# Lipo_Rider_Plus.net
KiCad netlist of a schematic drawn in EAGLE
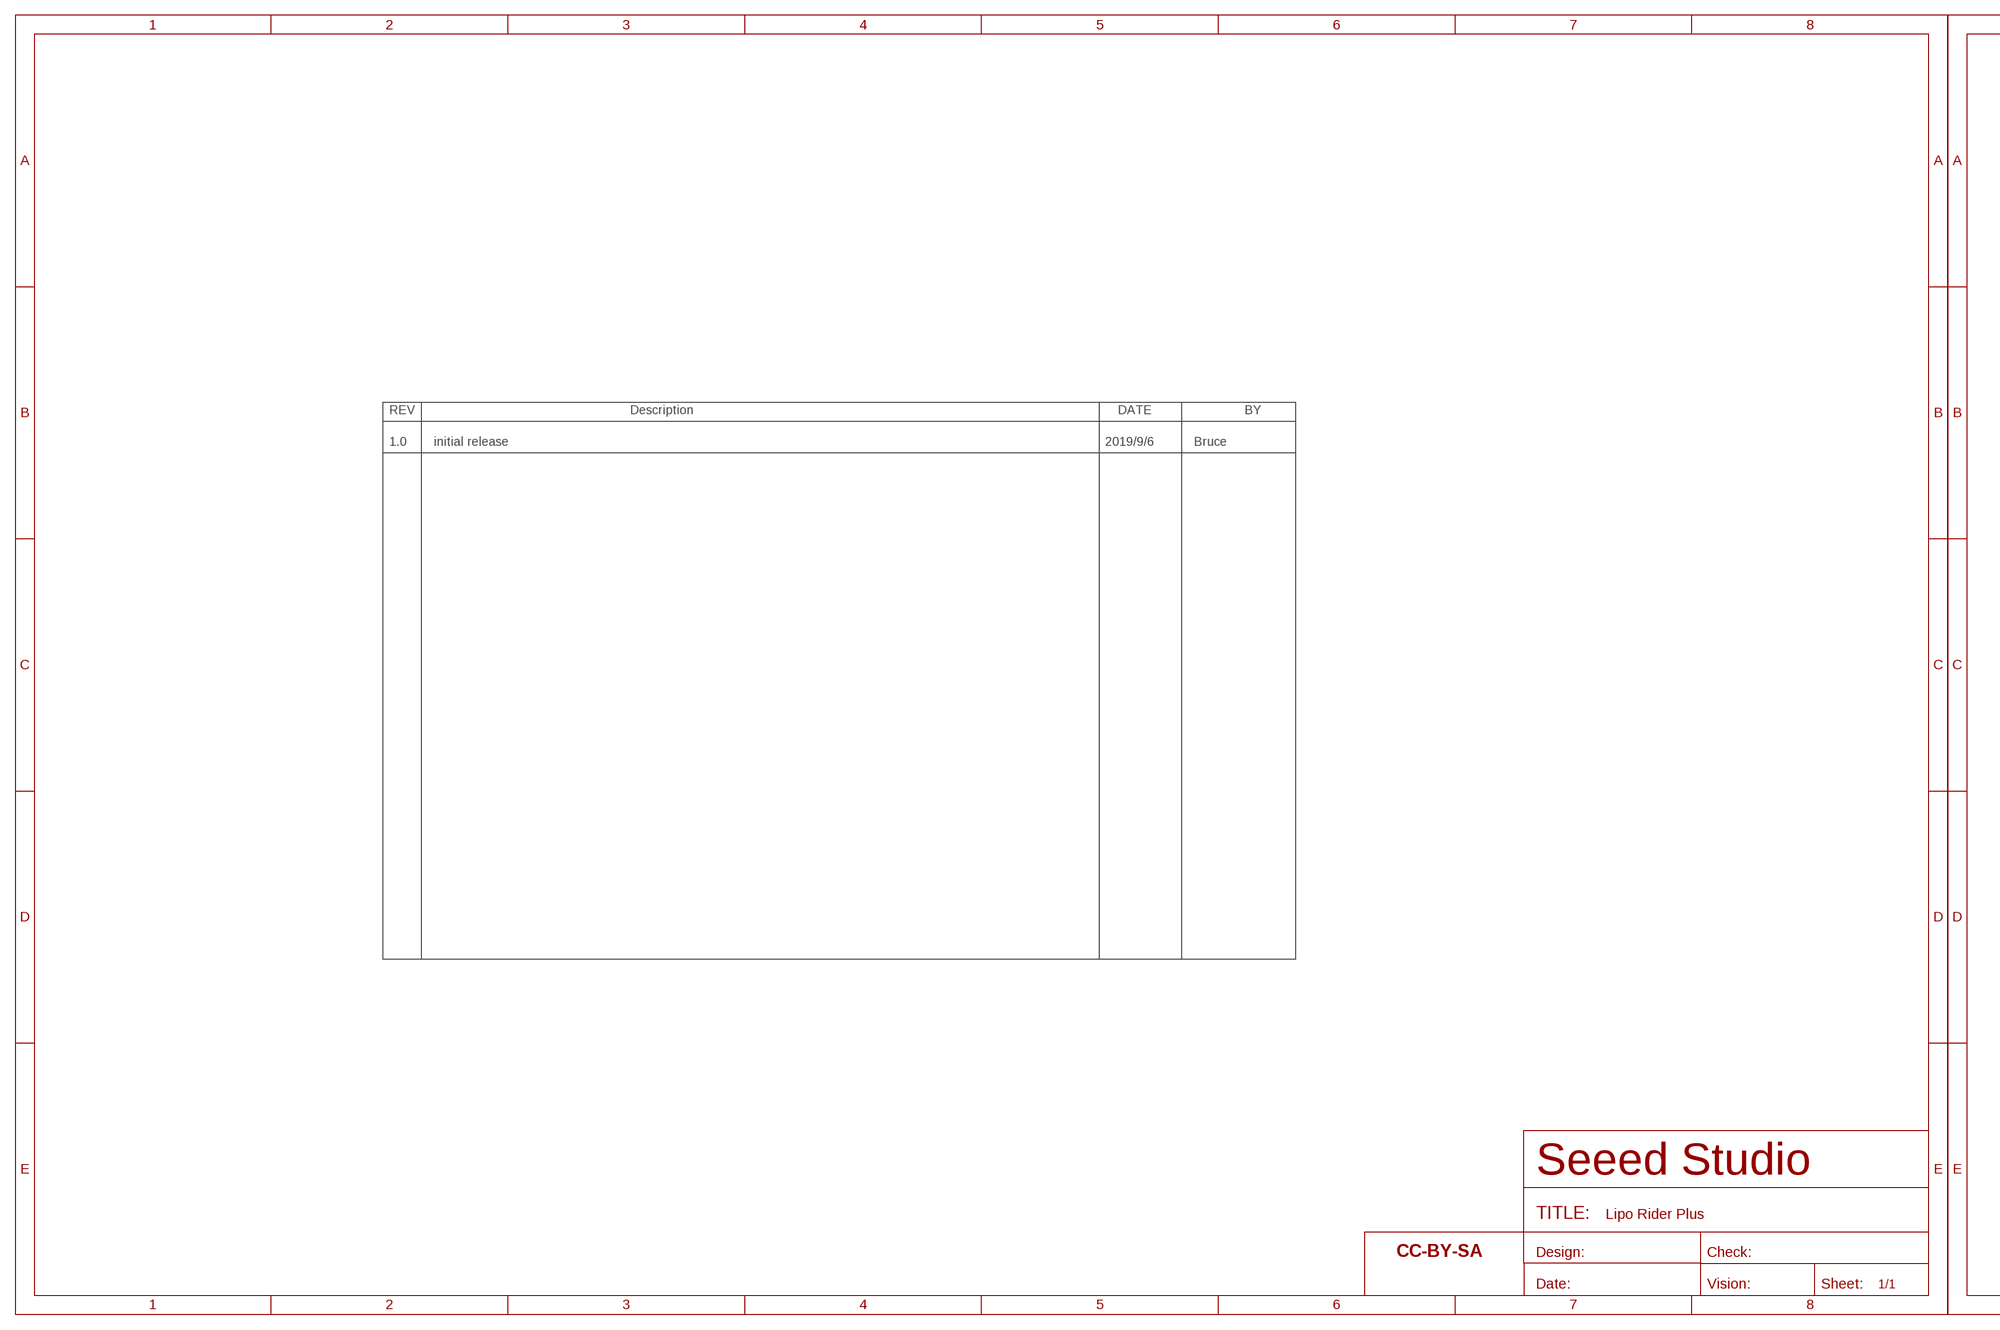
[diagram p0: schematic, sheet 1, part 1 of 2]
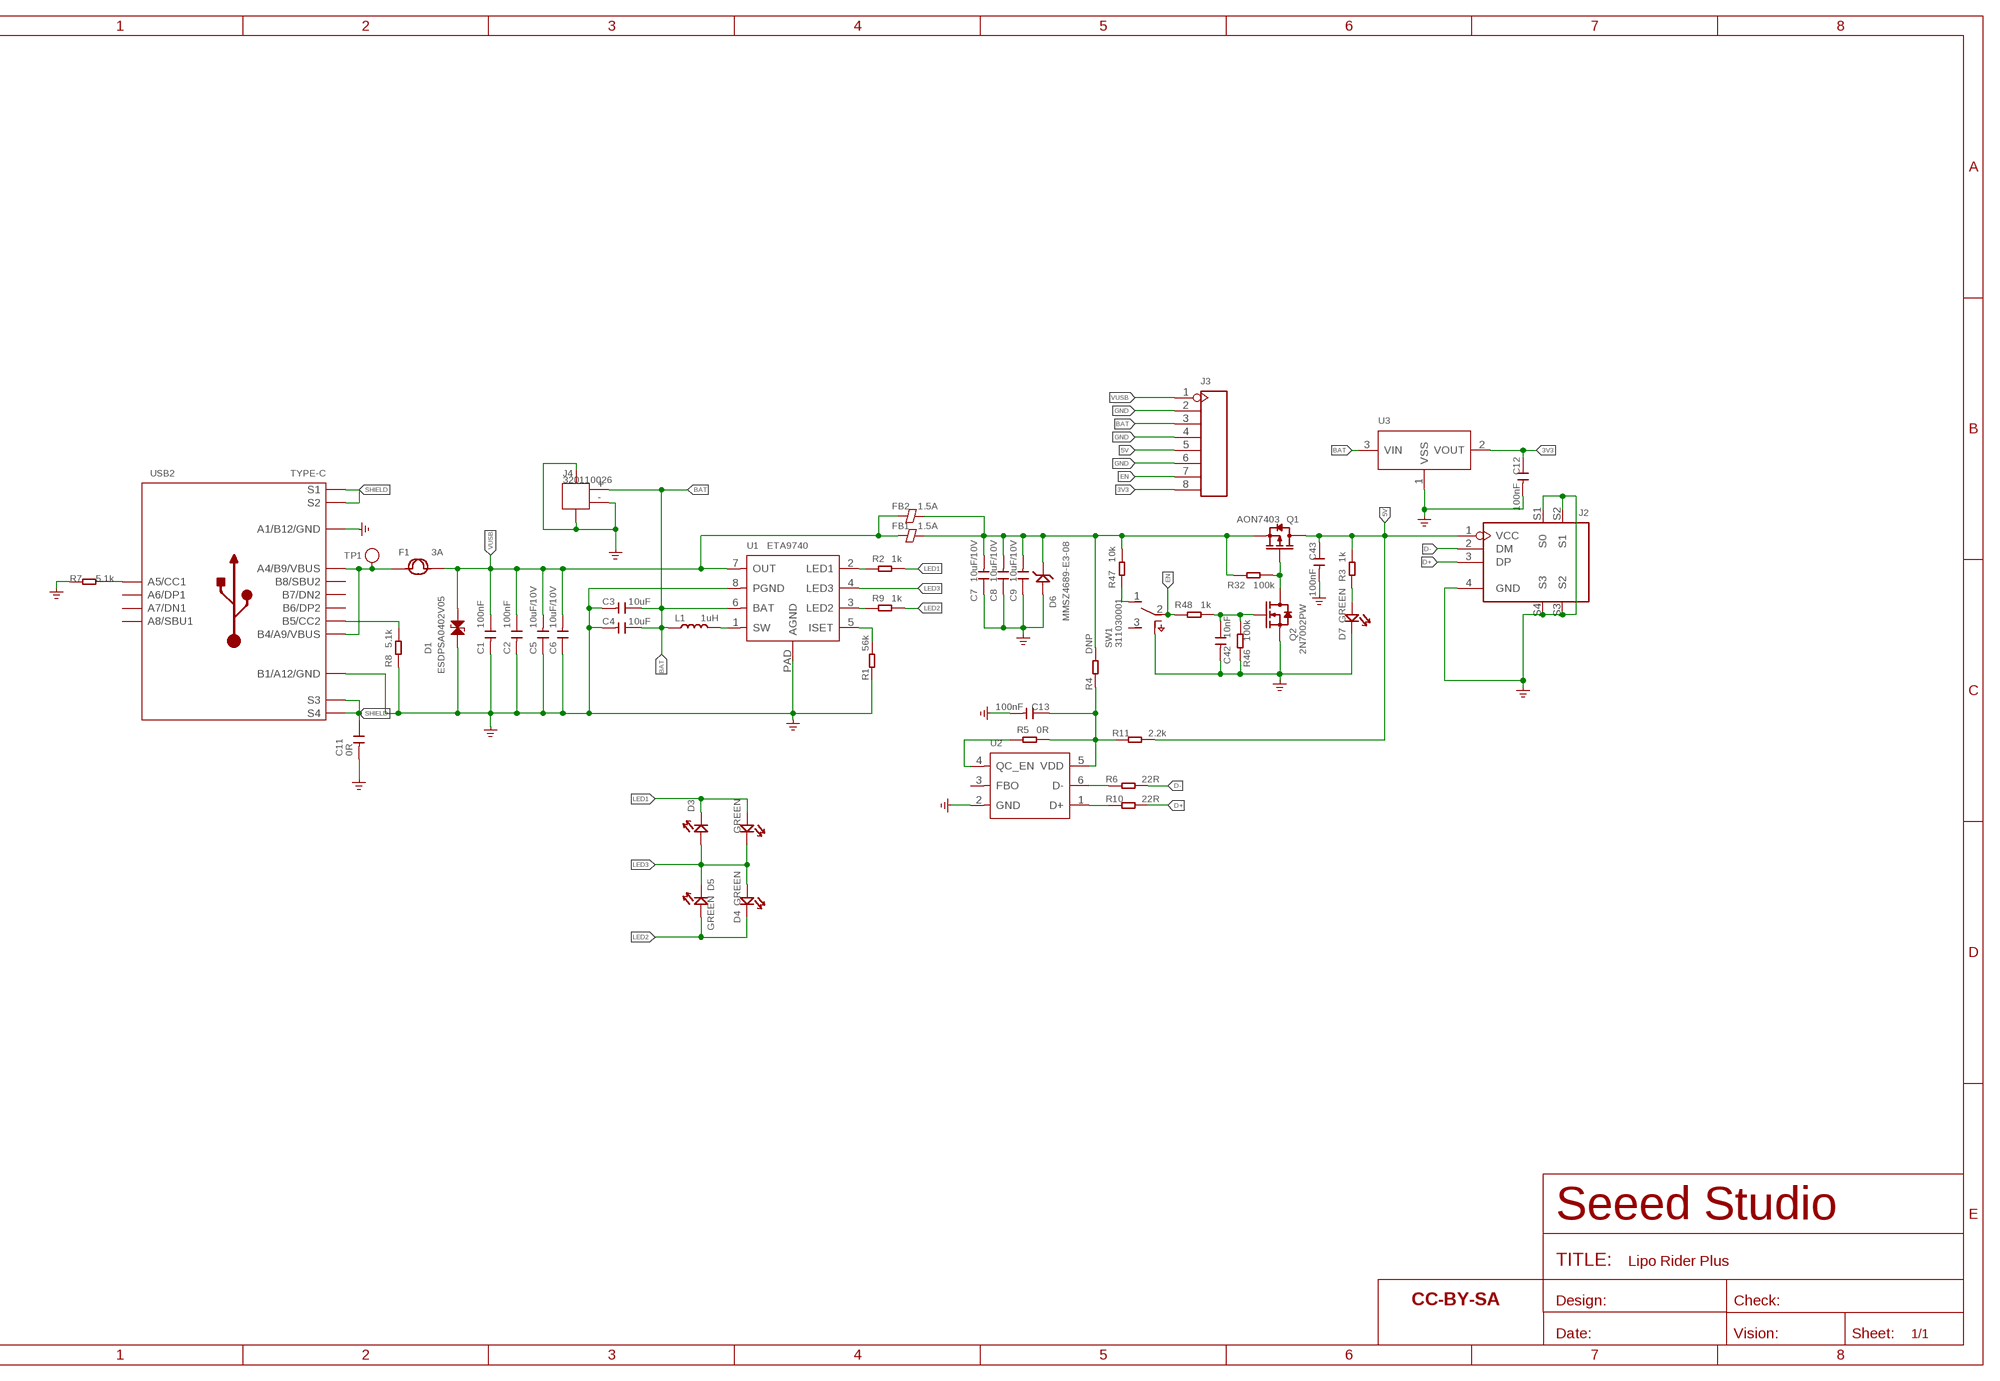
[diagram p1: schematic, sheet 1, part 2 of 2]

(export (version "E")
  (design (tool "Eeschema 10.0.6"))
  (components
    (comp (ref "C1")
      (value "100nF")
      (footprint "eagle-import:C0402")
      (libsource (lib "eagle-import") (part "CAP-0402"))
    )
    (comp (ref "C2")
      (value "100nF")
      (footprint "eagle-import:C0402")
      (libsource (lib "eagle-import") (part "CAP-0402"))
    )
    (comp (ref "C3")
      (value "10uF")
      (footprint "eagle-import:C0603")
      (libsource (lib "eagle-import") (part "CAP-0603"))
    )
    (comp (ref "C4")
      (value "10uF")
      (footprint "eagle-import:C0603")
      (libsource (lib "eagle-import") (part "CAP-0603"))
    )
    (comp (ref "C5")
      (value "10uF/10V")
      (footprint "eagle-import:C0805")
      (libsource (lib "eagle-import") (part "CAP-0805"))
    )
    (comp (ref "C6")
      (value "10uF/10V")
      (footprint "eagle-import:C0805")
      (libsource (lib "eagle-import") (part "CAP-0805"))
    )
    (comp (ref "C7")
      (value "10uF/10V")
      (footprint "eagle-import:C0805")
      (libsource (lib "eagle-import") (part "CAP-0805"))
    )
    (comp (ref "C8")
      (value "10uF/10V")
      (footprint "eagle-import:C0805")
      (libsource (lib "eagle-import") (part "CAP-0805"))
    )
    (comp (ref "C9")
      (value "10uF/10V")
      (footprint "eagle-import:C0805")
      (libsource (lib "eagle-import") (part "CAP-0805"))
    )
    (comp (ref "C11")
      (value "0R")
      (footprint "eagle-import:C0402")
      (libsource (lib "eagle-import") (part "CAP-0402"))
    )
    (comp (ref "C12")
      (value "100nF")
      (footprint "eagle-import:C0402")
      (libsource (lib "eagle-import") (part "CAP-0402"))
    )
    (comp (ref "C13")
      (value "100nF")
      (footprint "eagle-import:C0402")
      (libsource (lib "eagle-import") (part "CAP-0402"))
    )
    (comp (ref "C42")
      (value "10nF")
      (footprint "eagle-import:C0402")
      (libsource (lib "eagle-import") (part "CAP-0402"))
    )
    (comp (ref "C43")
      (value "100nF")
      (footprint "eagle-import:C0402")
      (libsource (lib "eagle-import") (part "CAP-0402"))
    )
    (comp (ref "D1")
      (value "ESDPSA0402V05")
      (footprint "eagle-import:ESD-0402")
      (libsource (lib "eagle-import") (part "D-ESD-2P-DOUBLE-0402"))
    )
    (comp (ref "D2")
      (value "GREEN")
      (footprint "eagle-import:LED-0402")
      (libsource (lib "eagle-import") (part "LED-0402"))
    )
    (comp (ref "D3")
      (value "GREEN")
      (footprint "eagle-import:LED-0402")
      (libsource (lib "eagle-import") (part "LED-0402"))
    )
    (comp (ref "D4")
      (value "GREEN")
      (footprint "eagle-import:LED-0402")
      (libsource (lib "eagle-import") (part "LED-0402"))
    )
    (comp (ref "D5")
      (value "GREEN")
      (footprint "eagle-import:LED-0402")
      (libsource (lib "eagle-import") (part "LED-0402"))
    )
    (comp (ref "D6")
      (value "MMSZ4689-E3-08")
      (footprint "eagle-import:SOD-123")
      (libsource (lib "eagle-import") (part "D-ZENER-2P-304030008"))
    )
    (comp (ref "D7")
      (value "GREEN")
      (footprint "eagle-import:LED-0402")
      (libsource (lib "eagle-import") (part "LED-0402"))
    )
    (comp (ref "F1")
      (value "3A")
      (footprint "eagle-import:F1812")
      (libsource (lib "eagle-import") (part "FUSE'1812'"))
    )
    (comp (ref "FB1")
      (value "1.5A")
      (footprint "eagle-import:F0805")
      (libsource (lib "eagle-import") (part "FERRITE-BEAD-0805"))
    )
    (comp (ref "FB2")
      (value "1.5A")
      (footprint "eagle-import:F0805")
      (libsource (lib "eagle-import") (part "FERRITE-BEAD-0805"))
    )
    (comp (ref "FR1")
      (value "SEEEDSTUDIO-OPEN-SCH-FRAME-BIG")
      (footprint "eagle-import:SEEEDSTUDIO-PCB-FRAME")
      (libsource (lib "eagle-import") (part "SEEEDSTUDIO-OPEN-SCH-FRAME-BIG"))
    )
    (comp (ref "FR2")
      (value "SEEEDSTUDIO-OPEN-SCH-FRAME-BIG")
      (footprint "eagle-import:SEEEDSTUDIO-PCB-FRAME")
      (libsource (lib "eagle-import") (part "SEEEDSTUDIO-OPEN-SCH-FRAME-BIG"))
    )
    (comp (ref "J2")
      (value "USB4+4P-SMD+DIP")
      (footprint "eagle-import:USB4+4P-2.0-14.6X10.6X5.72MM")
      (libsource (lib "eagle-import") (part "USB4+4P-SMD+DIP"))
    )
    (comp (ref "J3")
      (value "HEADER-8P-65/35MIL")
      (footprint "eagle-import:H8-2.54-C65D35MIL")
      (libsource (lib "eagle-import") (part "HEADER-8P-65/35MIL"))
    )
    (comp (ref "J4")
      (value "320110026")
      (footprint "eagle-import:HW2-SMD-2.0-90D")
      (libsource (lib "eagle-import") (part "JST-2P-SMD'2.0'"))
    )
    (comp (ref "L1")
      (value "1uH")
      (footprint "eagle-import:L4.4X3.0MM")
      (libsource (lib "eagle-import") (part "INDUCTOR-4430"))
    )
    (comp (ref "Q1")
      (value "AON7403")
      (footprint "eagle-import:DFN8P-0.65-3X3X0.8MM")
      (libsource (lib "eagle-import") (part "MOSFET-P-AON7403"))
    )
    (comp (ref "Q2")
      (value "2N7002PW")
      (footprint "eagle-import:SOT-323")
      (libsource (lib "eagle-import") (part "MOSFET-N'SI1304BDL'"))
    )
    (comp (ref "R1")
      (value "56k")
      (footprint "eagle-import:R0402")
      (libsource (lib "eagle-import") (part "RES-0402"))
    )
    (comp (ref "R2")
      (value "1k")
      (footprint "eagle-import:R0402")
      (libsource (lib "eagle-import") (part "RES-0402"))
    )
    (comp (ref "R3")
      (value "1k")
      (footprint "eagle-import:R0402")
      (libsource (lib "eagle-import") (part "RES-0402"))
    )
    (comp (ref "R4")
      (value "DNP")
      (footprint "eagle-import:R0402")
      (libsource (lib "eagle-import") (part "RES-0402"))
    )
    (comp (ref "R5")
      (value "0R")
      (footprint "eagle-import:R0402")
      (libsource (lib "eagle-import") (part "RES-0402"))
    )
    (comp (ref "R6")
      (value "22R")
      (footprint "eagle-import:R0402")
      (libsource (lib "eagle-import") (part "RES-0402"))
    )
    (comp (ref "R7")
      (value "5.1k")
      (footprint "eagle-import:R0402")
      (libsource (lib "eagle-import") (part "RES-0402"))
    )
    (comp (ref "R8")
      (value "5.1k")
      (footprint "eagle-import:R0402")
      (libsource (lib "eagle-import") (part "RES-0402"))
    )
    (comp (ref "R9")
      (value "1k")
      (footprint "eagle-import:R0402")
      (libsource (lib "eagle-import") (part "RES-0402"))
    )
    (comp (ref "R10")
      (value "22R")
      (footprint "eagle-import:R0402")
      (libsource (lib "eagle-import") (part "RES-0402"))
    )
    (comp (ref "R11")
      (value "2.2k")
      (footprint "eagle-import:R0402")
      (libsource (lib "eagle-import") (part "RES-0402"))
    )
    (comp (ref "R32")
      (value "100k")
      (footprint "eagle-import:R0402")
      (libsource (lib "eagle-import") (part "RES-0402"))
    )
    (comp (ref "R46")
      (value "100k")
      (footprint "eagle-import:R0402")
      (libsource (lib "eagle-import") (part "RES-0402"))
    )
    (comp (ref "R47")
      (value "10k")
      (footprint "eagle-import:R0402")
      (libsource (lib "eagle-import") (part "RES-0402"))
    )
    (comp (ref "R48")
      (value "1k")
      (footprint "eagle-import:R0402")
      (libsource (lib "eagle-import") (part "RES-0402"))
    )
    (comp (ref "SW1")
      (value "311030001")
      (footprint "eagle-import:SW7-SMD-L6.7X2.7X3.2MM")
      (libsource (lib "eagle-import") (part "SWITCH-3+4P-311030001"))
    )
    (comp (ref "TP1")
      (value "TEST")
      (footprint "eagle-import:TP-D45MIL")
      (fields (field (name "PARTNO") "DNP"))
      (libsource (lib "eagle-import") (part "TEST-POINT'4545'"))
    )
    (comp (ref "U1")
      (value "ETA9740")
      (footprint "eagle-import:ESOP8L-1.27-5X3.9MM")
      (libsource (lib "eagle-import") (part "PMIC-ETA9740"))
    )
    (comp (ref "U2")
      (value "CONTROLLER-FP6601Q")
      (footprint "eagle-import:SOT-23-6")
      (libsource (lib "eagle-import") (part "CONTROLLER-FP6601Q"))
    )
    (comp (ref "U3")
      (value "PMIC-XC6206PMR")
      (footprint "eagle-import:SOT-23")
      (libsource (lib "eagle-import") (part "PMIC-XC6206PMR"))
    )
    (comp (ref "USB2")
      (value "TYPE-C")
      (footprint "eagle-import:USB2.0-TYPE-C")
      (libsource (lib "eagle-import") (part "USB2.0-TYPE-C"))
    )
  )
  (nets
    (net (code "1") (name "3V3") (class "Default")
      (node (ref "C12") (pin "1") (pinfunction "1_1") (pintype "passive"))
      (node (ref "J3") (pin "8") (pinfunction "8_8") (pintype "bidirectional"))
      (node (ref "U3") (pin "2") (pinfunction "VOUT_2") (pintype "bidirectional"))
    )
    (net (code "2") (name "5V") (class "Default")
      (node (ref "C43") (pin "1") (pinfunction "1_1") (pintype "passive"))
      (node (ref "J2") (pin "1") (pinfunction "VCC_1") (pintype "bidirectional"))
      (node (ref "J3") (pin "5") (pinfunction "5_5") (pintype "bidirectional"))
      (node (ref "Q1") (pin "5") (pinfunction "D_5") (pintype "passive"))
      (node (ref "Q1") (pin "6") (pinfunction "D_6") (pintype "passive"))
      (node (ref "Q1") (pin "7") (pinfunction "D_7") (pintype "passive"))
      (node (ref "Q1") (pin "8") (pinfunction "D_8") (pintype "passive"))
      (node (ref "Q1") (pin "9") (pinfunction "D_9") (pintype "passive"))
      (node (ref "R11") (pin "2") (pinfunction "2_2") (pintype "passive"))
      (node (ref "R3") (pin "2") (pinfunction "2_2") (pintype "passive"))
    )
    (net (code "3") (name "BAT") (class "Default")
      (node (ref "C3") (pin "1") (pinfunction "1_1") (pintype "passive"))
      (node (ref "C4") (pin "1") (pinfunction "1_1") (pintype "passive"))
      (node (ref "J3") (pin "3") (pinfunction "3_3") (pintype "bidirectional"))
      (node (ref "J4") (pin "+") (pinfunction "1_+") (pintype "bidirectional"))
      (node (ref "L1") (pin "1") (pinfunction "1_1") (pintype "passive"))
      (node (ref "U1") (pin "6") (pinfunction "BAT_6") (pintype "bidirectional"))
      (node (ref "U3") (pin "3") (pinfunction "VIN_3") (pintype "bidirectional"))
    )
    (net (code "4") (name "D+") (class "Default")
      (node (ref "J2") (pin "3") (pinfunction "DP_3") (pintype "bidirectional"))
      (node (ref "R10") (pin "2") (pinfunction "2_2") (pintype "passive"))
    )
    (net (code "5") (name "D-") (class "Default")
      (node (ref "J2") (pin "2") (pinfunction "DM_2") (pintype "bidirectional"))
      (node (ref "R6") (pin "2") (pinfunction "2_2") (pintype "passive"))
    )
    (net (code "6") (name "EN") (class "Default")
      (node (ref "J3") (pin "7") (pinfunction "7_7") (pintype "bidirectional"))
      (node (ref "R48") (pin "1") (pinfunction "1_1") (pintype "passive"))
      (node (ref "SW1") (pin "2") (pinfunction "COM_2") (pintype "bidirectional"))
    )
    (net (code "7") (name "GND") (class "Default")
      (node (ref "C1") (pin "2") (pinfunction "2_2") (pintype "passive"))
      (node (ref "C11") (pin "2") (pinfunction "2_2") (pintype "passive"))
      (node (ref "C12") (pin "2") (pinfunction "2_2") (pintype "passive"))
      (node (ref "C13") (pin "2") (pinfunction "2_2") (pintype "passive"))
      (node (ref "C2") (pin "2") (pinfunction "2_2") (pintype "passive"))
      (node (ref "C3") (pin "2") (pinfunction "2_2") (pintype "passive"))
      (node (ref "C4") (pin "2") (pinfunction "2_2") (pintype "passive"))
      (node (ref "C42") (pin "2") (pinfunction "2_2") (pintype "passive"))
      (node (ref "C43") (pin "2") (pinfunction "2_2") (pintype "passive"))
      (node (ref "C5") (pin "1") (pinfunction "1_1") (pintype "passive"))
      (node (ref "C6") (pin "1") (pinfunction "1_1") (pintype "passive"))
      (node (ref "C7") (pin "1") (pinfunction "1_1") (pintype "passive"))
      (node (ref "C8") (pin "1") (pinfunction "1_1") (pintype "passive"))
      (node (ref "C9") (pin "1") (pinfunction "1_1") (pintype "passive"))
      (node (ref "D1") (pin "1") (pinfunction "1_1") (pintype "bidirectional"))
      (node (ref "D6") (pin "+") (pinfunction "+_+") (pintype "bidirectional"))
      (node (ref "D7") (pin "-") (pinfunction "-_-") (pintype "passive"))
      (node (ref "J2") (pin "4") (pinfunction "GND_4") (pintype "bidirectional"))
      (node (ref "J2") (pin "S1") (pinfunction "S0_S1") (pintype "bidirectional"))
      (node (ref "J2") (pin "S2") (pinfunction "S1_S2") (pintype "bidirectional"))
      (node (ref "J2") (pin "S3") (pinfunction "S2_S3") (pintype "bidirectional"))
      (node (ref "J2") (pin "S4") (pinfunction "S3_S4") (pintype "bidirectional"))
      (node (ref "J3") (pin "2") (pinfunction "2_2") (pintype "bidirectional"))
      (node (ref "J3") (pin "4") (pinfunction "4_4") (pintype "bidirectional"))
      (node (ref "J3") (pin "6") (pinfunction "6_6") (pintype "bidirectional"))
      (node (ref "J4") (pin "-") (pinfunction "2_-") (pintype "bidirectional"))
      (node (ref "J4") (pin "3") (pinfunction "3_3") (pintype "bidirectional"))
      (node (ref "J4") (pin "4") (pinfunction "4_4") (pintype "bidirectional"))
      (node (ref "Q2") (pin "2") (pinfunction "S_2") (pintype "passive"))
      (node (ref "R1") (pin "1") (pinfunction "1_1") (pintype "passive"))
      (node (ref "R46") (pin "1") (pinfunction "1_1") (pintype "passive"))
      (node (ref "R7") (pin "1") (pinfunction "1_1") (pintype "passive"))
      (node (ref "R8") (pin "2") (pinfunction "2_2") (pintype "passive"))
      (node (ref "SW1") (pin "SS1") (pinfunction "SS2_SS1") (pintype "bidirectional"))
      (node (ref "SW1") (pin "SS2") (pinfunction "SS2_SS2") (pintype "bidirectional"))
      (node (ref "SW1") (pin "SS3") (pinfunction "SS2_SS3") (pintype "bidirectional"))
      (node (ref "SW1") (pin "SS4") (pinfunction "SS2_SS4") (pintype "bidirectional"))
      (node (ref "U1") (pin "8") (pinfunction "PGND_8") (pintype "bidirectional"))
      (node (ref "U1") (pin "PAD") (pinfunction "AGND_PAD") (pintype "bidirectional"))
      (node (ref "U2") (pin "2") (pinfunction "GND_2") (pintype "bidirectional"))
      (node (ref "U3") (pin "1") (pinfunction "VSS_1") (pintype "bidirectional"))
      (node (ref "USB2") (pin "A1_B12") (pinfunction "A1/B12/GND_A1_B12") (pintype "bidirectional"))
      (node (ref "USB2") (pin "B1_A12") (pinfunction "B1/A12/GND_B1_A12") (pintype "bidirectional"))
    )
    (net (code "8") (name "LED1") (class "Default")
      (node (ref "D2") (pin "+") (pinfunction "+_+") (pintype "passive"))
      (node (ref "D3") (pin "-") (pinfunction "-_-") (pintype "passive"))
      (node (ref "R2") (pin "2") (pinfunction "2_2") (pintype "passive"))
    )
    (net (code "9") (name "LED2") (class "Default")
      (node (ref "D4") (pin "-") (pinfunction "-_-") (pintype "passive"))
      (node (ref "D5") (pin "+") (pinfunction "+_+") (pintype "passive"))
      (node (ref "R9") (pin "2") (pinfunction "2_2") (pintype "passive"))
    )
    (net (code "10") (name "LED3") (class "Default")
      (node (ref "D2") (pin "-") (pinfunction "-_-") (pintype "passive"))
      (node (ref "D3") (pin "+") (pinfunction "+_+") (pintype "passive"))
      (node (ref "D4") (pin "+") (pinfunction "+_+") (pintype "passive"))
      (node (ref "D5") (pin "-") (pinfunction "-_-") (pintype "passive"))
      (node (ref "U1") (pin "4") (pinfunction "LED3_4") (pintype "bidirectional"))
    )
    (net (code "11") (name "Net-(C7-Pad2)") (class "Default")
      (node (ref "C7") (pin "2") (pinfunction "2_2") (pintype "passive"))
      (node (ref "C8") (pin "2") (pinfunction "2_2") (pintype "passive"))
      (node (ref "C9") (pin "2") (pinfunction "2_2") (pintype "passive"))
      (node (ref "D6") (pin "-") (pinfunction "-_-") (pintype "bidirectional"))
      (node (ref "FB1") (pin "2") (pinfunction "2_2") (pintype "bidirectional"))
      (node (ref "FB2") (pin "2") (pinfunction "2_2") (pintype "bidirectional"))
      (node (ref "Q1") (pin "1") (pinfunction "S_1") (pintype "passive"))
      (node (ref "Q1") (pin "2") (pinfunction "S_2") (pintype "passive"))
      (node (ref "Q1") (pin "3") (pinfunction "S_3") (pintype "passive"))
      (node (ref "R32") (pin "1") (pinfunction "1_1") (pintype "passive"))
      (node (ref "R4") (pin "2") (pinfunction "2_2") (pintype "passive"))
      (node (ref "R47") (pin "2") (pinfunction "2_2") (pintype "passive"))
    )
    (net (code "12") (name "Net-(D7-Pad+)") (class "Default")
      (node (ref "D7") (pin "+") (pinfunction "+_+") (pintype "passive"))
      (node (ref "R3") (pin "1") (pinfunction "1_1") (pintype "passive"))
    )
    (net (code "13") (name "Net-(Q1-G)") (class "Default")
      (node (ref "Q1") (pin "4") (pinfunction "G_4") (pintype "passive"))
      (node (ref "Q2") (pin "3") (pinfunction "D_3") (pintype "passive"))
      (node (ref "R32") (pin "2") (pinfunction "2_2") (pintype "passive"))
    )
    (net (code "14") (name "Net-(Q2-G)") (class "Default")
      (node (ref "C42") (pin "1") (pinfunction "1_1") (pintype "passive"))
      (node (ref "Q2") (pin "1") (pinfunction "G_1") (pintype "passive"))
      (node (ref "R46") (pin "2") (pinfunction "2_2") (pintype "passive"))
      (node (ref "R48") (pin "2") (pinfunction "2_2") (pintype "passive"))
    )
    (net (code "15") (name "Net-(SW1-A)") (class "Default")
      (node (ref "R47") (pin "1") (pinfunction "1_1") (pintype "passive"))
      (node (ref "SW1") (pin "1") (pinfunction "A_1") (pintype "bidirectional"))
    )
    (net (code "16") (name "Net-(U1-ISET)") (class "Default")
      (node (ref "R1") (pin "2") (pinfunction "2_2") (pintype "passive"))
      (node (ref "U1") (pin "5") (pinfunction "ISET_5") (pintype "bidirectional"))
    )
    (net (code "17") (name "Net-(U1-LED1)") (class "Default")
      (node (ref "R2") (pin "1") (pinfunction "1_1") (pintype "passive"))
      (node (ref "U1") (pin "2") (pinfunction "LED1_2") (pintype "bidirectional"))
    )
    (net (code "18") (name "Net-(U1-LED2)") (class "Default")
      (node (ref "R9") (pin "1") (pinfunction "1_1") (pintype "passive"))
      (node (ref "U1") (pin "3") (pinfunction "LED2_3") (pintype "bidirectional"))
    )
    (net (code "19") (name "Net-(U1-SW)") (class "Default")
      (node (ref "L1") (pin "2") (pinfunction "2_2") (pintype "passive"))
      (node (ref "U1") (pin "1") (pinfunction "SW_1") (pintype "bidirectional"))
    )
    (net (code "20") (name "Net-(U2-D+)") (class "Default")
      (node (ref "R10") (pin "1") (pinfunction "1_1") (pintype "passive"))
      (node (ref "U2") (pin "1") (pinfunction "D+_1") (pintype "bidirectional"))
    )
    (net (code "21") (name "Net-(U2-D-)") (class "Default")
      (node (ref "R6") (pin "1") (pinfunction "1_1") (pintype "passive"))
      (node (ref "U2") (pin "6") (pinfunction "D-_6") (pintype "bidirectional"))
    )
    (net (code "22") (name "Net-(U2-QC_EN)") (class "Default")
      (node (ref "R5") (pin "1") (pinfunction "1_1") (pintype "passive"))
      (node (ref "U2") (pin "4") (pinfunction "QC_EN_4") (pintype "bidirectional"))
    )
    (net (code "23") (name "Net-(U2-VDD)") (class "Default")
      (node (ref "C13") (pin "1") (pinfunction "1_1") (pintype "passive"))
      (node (ref "R11") (pin "1") (pinfunction "1_1") (pintype "passive"))
      (node (ref "R4") (pin "1") (pinfunction "1_1") (pintype "passive"))
      (node (ref "R5") (pin "2") (pinfunction "2_2") (pintype "passive"))
      (node (ref "U2") (pin "5") (pinfunction "VDD_5") (pintype "bidirectional"))
    )
    (net (code "24") (name "Net-(USB2-A4{slash}B9{slash}VBUS)") (class "Default")
      (node (ref "F1") (pin "1") (pinfunction "1_1") (pintype "bidirectional"))
      (node (ref "TP1") (pin "T") (pinfunction "T_T") (pintype "bidirectional"))
      (node (ref "USB2") (pin "A4_B9") (pinfunction "A4/B9/VBUS_A4_B9") (pintype "bidirectional"))
      (node (ref "USB2") (pin "B4_A9") (pinfunction "B4/A9/VBUS_B4_A9") (pintype "bidirectional"))
    )
    (net (code "25") (name "Net-(USB2-A5{slash}CC1)") (class "Default")
      (node (ref "R7") (pin "2") (pinfunction "2_2") (pintype "passive"))
      (node (ref "USB2") (pin "A5") (pinfunction "A5/CC1_A5") (pintype "bidirectional"))
    )
    (net (code "26") (name "Net-(USB2-B5{slash}CC2)") (class "Default")
      (node (ref "R8") (pin "1") (pinfunction "1_1") (pintype "passive"))
      (node (ref "USB2") (pin "B5") (pinfunction "B5/CC2_B5") (pintype "bidirectional"))
    )
    (net (code "27") (name "SHIELD") (class "Default")
      (node (ref "C11") (pin "1") (pinfunction "1_1") (pintype "passive"))
      (node (ref "USB2") (pin "S1") (pinfunction "S1_S1") (pintype "bidirectional"))
      (node (ref "USB2") (pin "S2") (pinfunction "S2_S2") (pintype "bidirectional"))
      (node (ref "USB2") (pin "S3") (pinfunction "S3_S3") (pintype "bidirectional"))
      (node (ref "USB2") (pin "S4") (pinfunction "S4_S4") (pintype "bidirectional"))
      (node (ref "USB2") (pin "S5") (pinfunction "S1_S5") (pintype "bidirectional"))
      (node (ref "USB2") (pin "S6") (pinfunction "S2_S6") (pintype "bidirectional"))
    )
    (net (code "28") (name "VUSB") (class "Default")
      (node (ref "C1") (pin "1") (pinfunction "1_1") (pintype "passive"))
      (node (ref "C2") (pin "1") (pinfunction "1_1") (pintype "passive"))
      (node (ref "C5") (pin "2") (pinfunction "2_2") (pintype "passive"))
      (node (ref "C6") (pin "2") (pinfunction "2_2") (pintype "passive"))
      (node (ref "D1") (pin "2") (pinfunction "2_2") (pintype "bidirectional"))
      (node (ref "F1") (pin "2") (pinfunction "2_2") (pintype "bidirectional"))
      (node (ref "FB1") (pin "1") (pinfunction "1_1") (pintype "bidirectional"))
      (node (ref "FB2") (pin "1") (pinfunction "1_1") (pintype "bidirectional"))
      (node (ref "J3") (pin "1") (pinfunction "1_1") (pintype "bidirectional"))
      (node (ref "U1") (pin "7") (pinfunction "OUT_7") (pintype "bidirectional"))
    )
    (net (code "29") (name "unconnected-(SW1-B-Pad3)") (class "Default")
      (node (ref "SW1") (pin "3") (pinfunction "B_3") (pintype "bidirectional"))
    )
    (net (code "30") (name "unconnected-(U2-FBO-Pad3)") (class "Default")
      (node (ref "U2") (pin "3") (pinfunction "FBO_3") (pintype "bidirectional"))
    )
    (net (code "31") (name "unconnected-(USB2-A6{slash}DP1-PadA6)") (class "Default")
      (node (ref "USB2") (pin "A6") (pinfunction "A6/DP1_A6") (pintype "bidirectional"))
    )
    (net (code "32") (name "unconnected-(USB2-A7{slash}DN1-PadA7)") (class "Default")
      (node (ref "USB2") (pin "A7") (pinfunction "A7/DN1_A7") (pintype "bidirectional"))
    )
    (net (code "33") (name "unconnected-(USB2-A8{slash}SBU1-PadA8)") (class "Default")
      (node (ref "USB2") (pin "A8") (pinfunction "A8/SBU1_A8") (pintype "bidirectional"))
    )
    (net (code "34") (name "unconnected-(USB2-B6{slash}DP2-PadB6)") (class "Default")
      (node (ref "USB2") (pin "B6") (pinfunction "B6/DP2_B6") (pintype "bidirectional"))
    )
    (net (code "35") (name "unconnected-(USB2-B7{slash}DN2-PadB7)") (class "Default")
      (node (ref "USB2") (pin "B7") (pinfunction "B7/DN2_B7") (pintype "bidirectional"))
    )
    (net (code "36") (name "unconnected-(USB2-B8{slash}SBU2-PadB8)") (class "Default")
      (node (ref "USB2") (pin "B8") (pinfunction "B8/SBU2_B8") (pintype "bidirectional"))
    )
  )
)
